# AC-DC-Supply-M1.net
KiCad netlist of a schematic drawn in Altium Designer
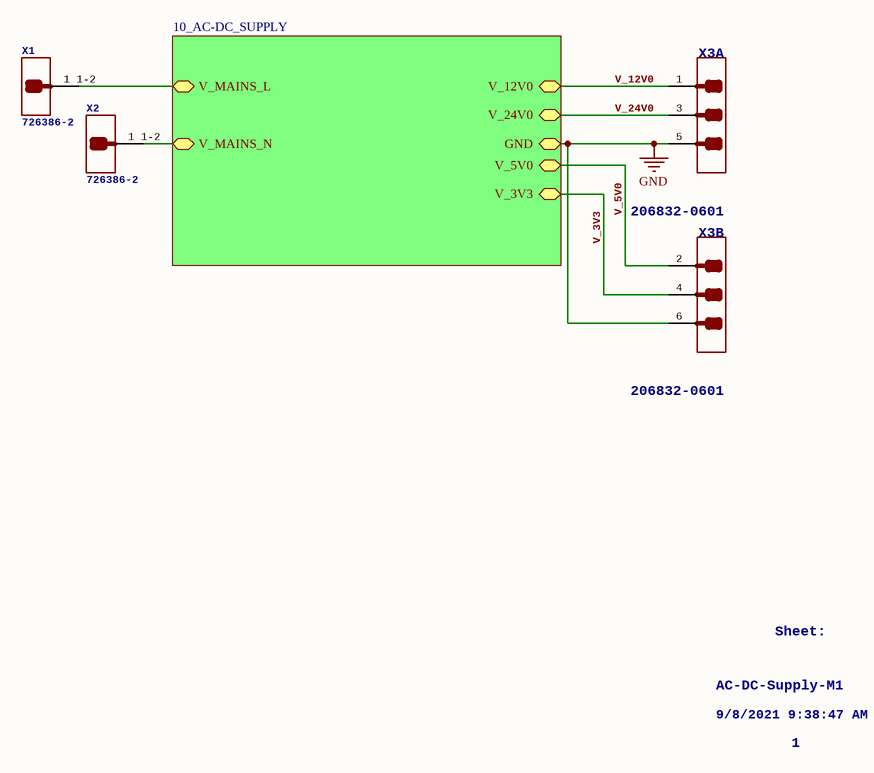
[diagram p0: AC-DC-Supply-M1.SchDoc]

(export (version "E")
  (design (tool "Eeschema 10.0.6"))
  (components
    (comp (ref "X1")
      (value "726386-2")
      (footprint "TE_726386-2_MODIFIED")
      (description "0.250\" (6.35mm) Quick Connect Male - Solder Connector Non-Insulated")
      (fields (field (name "MFR") "TE Connectivity") (field (name "LIBRARYNAME") "Labops_Lib_AH"))
      (libsource (lib "Labops_Lib_AH") (part "726386-2"))
    )
    (comp (ref "X2")
      (value "726386-2")
      (footprint "TE_726386-2_MODIFIED")
      (description "0.250\" (6.35mm) Quick Connect Male - Solder Connector Non-Insulated")
      (fields (field (name "MFR") "TE Connectivity") (field (name "LIBRARYNAME") "Labops_Lib_AH"))
      (libsource (lib "Labops_Lib_AH") (part "726386-2"))
    )
    (comp (ref "X3")
      (value "MOLEX_206832-0601MOLEX_206832-0601")
      (footprint "MOLEX_206832-0601")
      (description "Connector Header Through Hole 6 position 3mm Microfit")
      (fields
        (field (name "206832-0601") "206832-0601")
        (field (name "MFR") "Molex")
        (field (name "LIBRARYNAME") "Labops_Lib_AH")
      )
      (libsource (lib "Labops_Lib_AH") (part "MOLEX_206832-0601MOLEX_206832-0601"))
    )
  )
  (nets
    (net (code "1") (name "/V_3V3") (class "Default")
      (node (ref "X3") (pin "4") (pinfunction "4_4") (pintype "passive"))
    )
    (net (code "2") (name "/V_5V0") (class "Default")
      (node (ref "X3") (pin "2") (pinfunction "2_2") (pintype "passive"))
    )
    (net (code "3") (name "/V_12V0") (class "Default")
      (node (ref "X3") (pin "1") (pinfunction "1_1") (pintype "passive"))
    )
    (net (code "4") (name "/V_24V0") (class "Default")
      (node (ref "X3") (pin "3") (pinfunction "3_3") (pintype "passive"))
    )
    (net (code "5") (name "/V_MAINS_L") (class "Default")
      (node (ref "X1") (pin "1_1-2") (pinfunction "1_1_1-2") (pintype "passive"))
    )
    (net (code "6") (name "/V_MAINS_N") (class "Default")
      (node (ref "X2") (pin "1_1-2") (pinfunction "1_1_1-2") (pintype "passive"))
    )
    (net (code "7") (name "GND") (class "Default")
      (node (ref "X3") (pin "5") (pinfunction "5_5") (pintype "passive"))
      (node (ref "X3") (pin "6") (pinfunction "6_6") (pintype "passive"))
    )
  )
)
